# m328p.net
KiCad netlist of a schematic drawn in EAGLE
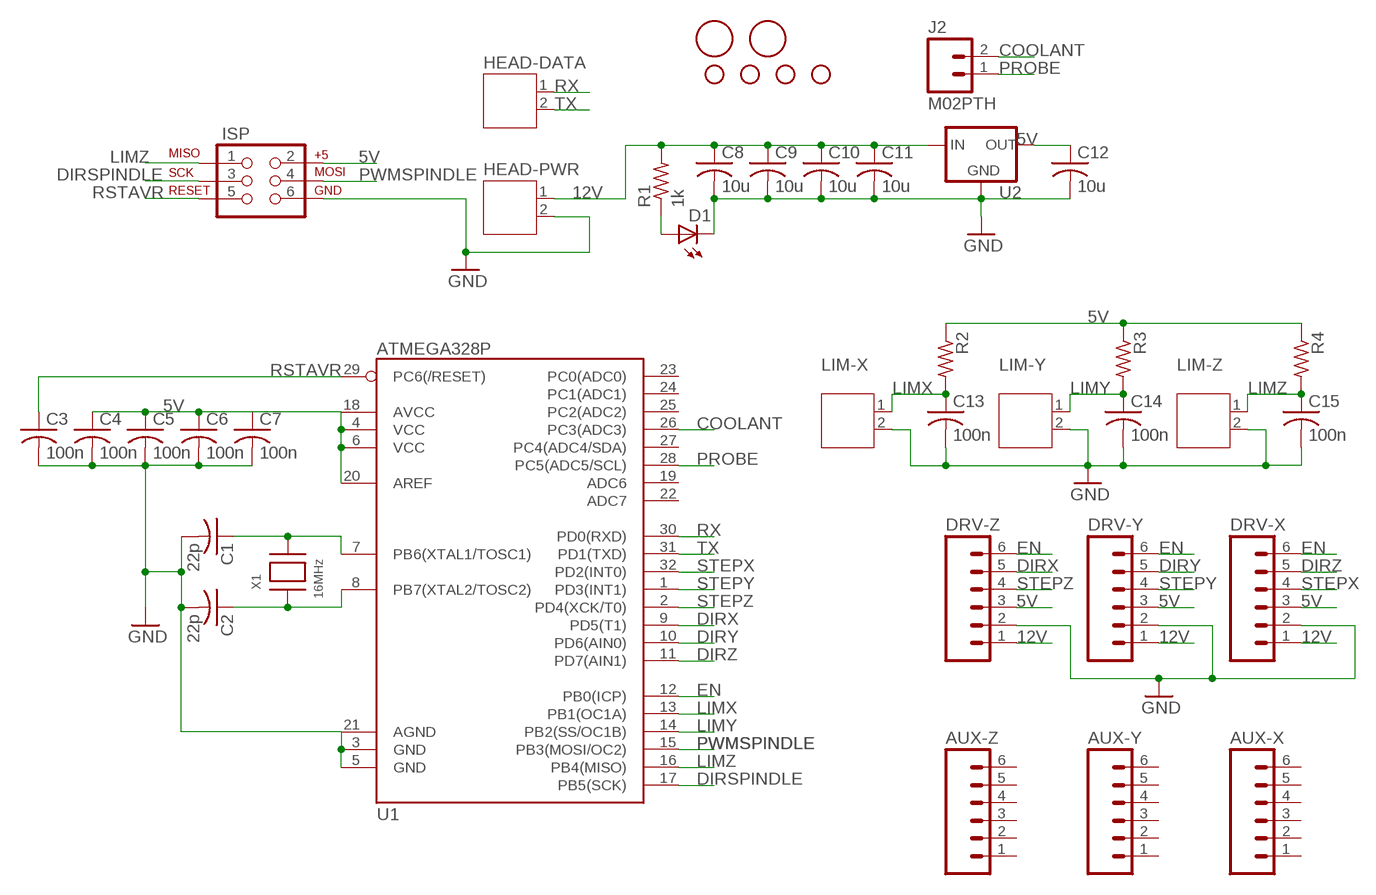
[diagram p0: schematic, sheet 1]

(export (version "E")
  (design (tool "Eeschema 10.0.6"))
  (components
    (comp (ref "AUX-X")
      (value "M06LOCK")
      (footprint "eagle-import:1X06_LOCK")
      (libsource (lib "eagle-import") (part "M06LOCK"))
    )
    (comp (ref "AUX-Y")
      (value "M06LOCK")
      (footprint "eagle-import:1X06_LOCK")
      (libsource (lib "eagle-import") (part "M06LOCK"))
    )
    (comp (ref "AUX-Z")
      (value "M06LOCK")
      (footprint "eagle-import:1X06_LOCK")
      (libsource (lib "eagle-import") (part "M06LOCK"))
    )
    (comp (ref "C1")
      (value "22p")
      (footprint "eagle-import:C0603")
      (libsource (lib "eagle-import") (part "C-USC0603"))
    )
    (comp (ref "C2")
      (value "22p")
      (footprint "eagle-import:C0603")
      (libsource (lib "eagle-import") (part "C-USC0603"))
    )
    (comp (ref "C3")
      (value "100n")
      (footprint "eagle-import:C0603")
      (libsource (lib "eagle-import") (part "C-USC0603"))
    )
    (comp (ref "C4")
      (value "100n")
      (footprint "eagle-import:C0603")
      (libsource (lib "eagle-import") (part "C-USC0603"))
    )
    (comp (ref "C5")
      (value "100n")
      (footprint "eagle-import:C0603")
      (libsource (lib "eagle-import") (part "C-USC0603"))
    )
    (comp (ref "C6")
      (value "100n")
      (footprint "eagle-import:C0603")
      (libsource (lib "eagle-import") (part "C-USC0603"))
    )
    (comp (ref "C7")
      (value "100n")
      (footprint "eagle-import:C0603")
      (libsource (lib "eagle-import") (part "C-USC0603"))
    )
    (comp (ref "C8")
      (value "10u")
      (footprint "eagle-import:C1206")
      (libsource (lib "eagle-import") (part "C-USC1206"))
    )
    (comp (ref "C9")
      (value "10u")
      (footprint "eagle-import:C1206")
      (libsource (lib "eagle-import") (part "C-USC1206"))
    )
    (comp (ref "C10")
      (value "10u")
      (footprint "eagle-import:C1206")
      (libsource (lib "eagle-import") (part "C-USC1206"))
    )
    (comp (ref "C11")
      (value "10u")
      (footprint "eagle-import:C1206")
      (libsource (lib "eagle-import") (part "C-USC1206"))
    )
    (comp (ref "C12")
      (value "10u")
      (footprint "eagle-import:C1206")
      (libsource (lib "eagle-import") (part "C-USC1206"))
    )
    (comp (ref "C13")
      (value "100n")
      (footprint "eagle-import:C0603")
      (libsource (lib "eagle-import") (part "C-USC0603"))
    )
    (comp (ref "C14")
      (value "100n")
      (footprint "eagle-import:C0603")
      (libsource (lib "eagle-import") (part "C-USC0603"))
    )
    (comp (ref "C15")
      (value "100n")
      (footprint "eagle-import:C0603")
      (libsource (lib "eagle-import") (part "C-USC0603"))
    )
    (comp (ref "D1")
      (value "LEDCHIPLED_1206")
      (footprint "eagle-import:CHIPLED_1206")
      (libsource (lib "eagle-import") (part "LEDCHIPLED_1206"))
    )
    (comp (ref "DRV-X")
      (value "M06LOCK")
      (footprint "eagle-import:1X06_LOCK")
      (libsource (lib "eagle-import") (part "M06LOCK"))
    )
    (comp (ref "DRV-Y")
      (value "M06LOCK")
      (footprint "eagle-import:1X06_LOCK")
      (libsource (lib "eagle-import") (part "M06LOCK"))
    )
    (comp (ref "DRV-Z")
      (value "M06LOCK")
      (footprint "eagle-import:1X06_LOCK")
      (libsource (lib "eagle-import") (part "M06LOCK"))
    )
    (comp (ref "HEAD-DATA")
      (value "JST-PH2")
      (footprint "eagle-import:JST-PH2")
      (libsource (lib "eagle-import") (part "JST-PH2"))
    )
    (comp (ref "HEAD-PWR")
      (value "JST-PH2")
      (footprint "eagle-import:JST-PH2")
      (libsource (lib "eagle-import") (part "JST-PH2"))
    )
    (comp (ref "ISP")
      (value "AVR_SPI_PRG_6PTH")
      (footprint "eagle-import:2X3")
      (libsource (lib "eagle-import") (part "AVR_SPI_PRG_6PTH"))
    )
    (comp (ref "J2")
      (value "M02PTH")
      (footprint "eagle-import:1X02")
      (libsource (lib "eagle-import") (part "M02PTH"))
    )
    (comp (ref "LIM-X")
      (value "JST-PH2")
      (footprint "eagle-import:JST-PH2")
      (libsource (lib "eagle-import") (part "JST-PH2"))
    )
    (comp (ref "LIM-Y")
      (value "JST-PH2")
      (footprint "eagle-import:JST-PH2")
      (libsource (lib "eagle-import") (part "JST-PH2"))
    )
    (comp (ref "LIM-Z")
      (value "JST-PH2")
      (footprint "eagle-import:JST-PH2")
      (libsource (lib "eagle-import") (part "JST-PH2"))
    )
    (comp (ref "R1")
      (value "1k")
      (footprint "eagle-import:R1206")
      (libsource (lib "eagle-import") (part "R-US_R1206"))
    )
    (comp (ref "R2")
      (value "R-US_R0603")
      (footprint "eagle-import:R0603")
      (libsource (lib "eagle-import") (part "R-US_R0603"))
    )
    (comp (ref "R3")
      (value "R-US_R0603")
      (footprint "eagle-import:R0603")
      (libsource (lib "eagle-import") (part "R-US_R0603"))
    )
    (comp (ref "R4")
      (value "R-US_R0603")
      (footprint "eagle-import:R0603")
      (libsource (lib "eagle-import") (part "R-US_R0603"))
    )
    (comp (ref "STANDOFF1")
      (value "STAND-OFFTIGHT")
      (footprint "eagle-import:STAND-OFF-TIGHT")
      (libsource (lib "eagle-import") (part "STAND-OFFTIGHT"))
    )
    (comp (ref "STANDOFF2")
      (value "STAND-OFFTIGHT")
      (footprint "eagle-import:STAND-OFF-TIGHT")
      (libsource (lib "eagle-import") (part "STAND-OFFTIGHT"))
    )
    (comp (ref "STANDOFF3")
      (value "STAND-OFFTIGHT")
      (footprint "eagle-import:STAND-OFF-TIGHT")
      (libsource (lib "eagle-import") (part "STAND-OFFTIGHT"))
    )
    (comp (ref "STANDOFF4")
      (value "STAND-OFFTIGHT")
      (footprint "eagle-import:STAND-OFF-TIGHT")
      (libsource (lib "eagle-import") (part "STAND-OFFTIGHT"))
    )
    (comp (ref "U$1")
      (value "FIDUCIAL")
      (footprint "eagle-import:FIDUCIAL_1MM")
      (libsource (lib "eagle-import") (part "FIDUCIAL"))
    )
    (comp (ref "U$2")
      (value "FIDUCIAL")
      (footprint "eagle-import:FIDUCIAL_1MM")
      (libsource (lib "eagle-import") (part "FIDUCIAL"))
    )
    (comp (ref "U1")
      (value "ATMEGA328P")
      (footprint "eagle-import:TQFP32-08")
      (libsource (lib "eagle-import") (part "ATMEGA328_SMT"))
    )
    (comp (ref "U2")
      (value "V_REG_MIC2920")
      (footprint "eagle-import:SOT223")
      (libsource (lib "eagle-import") (part "V_REG_MIC2920"))
    )
    (comp (ref "X1")
      (value "16MHz")
      (footprint "eagle-import:XTAL3215")
      (libsource (lib "eagle-import") (part "XTAL-3.2X1.5"))
    )
  )
  (nets
    (net (code "1") (name "/5V") (class "Default")
      (node (ref "C12") (pin "1") (pinfunction "1_1") (pintype "passive"))
      (node (ref "C4") (pin "1") (pinfunction "1_1") (pintype "passive"))
      (node (ref "C5") (pin "1") (pinfunction "1_1") (pintype "passive"))
      (node (ref "C6") (pin "1") (pinfunction "1_1") (pintype "passive"))
      (node (ref "C7") (pin "1") (pinfunction "1_1") (pintype "passive"))
      (node (ref "DRV-X") (pin "3") (pinfunction "3_3") (pintype "passive"))
      (node (ref "DRV-Y") (pin "3") (pinfunction "3_3") (pintype "passive"))
      (node (ref "DRV-Z") (pin "3") (pinfunction "3_3") (pintype "passive"))
      (node (ref "ISP") (pin "2") (pinfunction "2_2") (pintype "passive"))
      (node (ref "R2") (pin "1") (pinfunction "1_1") (pintype "passive"))
      (node (ref "R3") (pin "1") (pinfunction "1_1") (pintype "passive"))
      (node (ref "R4") (pin "1") (pinfunction "1_1") (pintype "passive"))
      (node (ref "U1") (pin "18") (pinfunction "AVCC_18") (pintype "bidirectional"))
      (node (ref "U1") (pin "20") (pinfunction "AREF_20") (pintype "bidirectional"))
      (node (ref "U1") (pin "4") (pinfunction "VCC_4") (pintype "bidirectional"))
      (node (ref "U1") (pin "6") (pinfunction "VCC_6") (pintype "bidirectional"))
      (node (ref "U2") (pin "3") (pinfunction "OUT_3") (pintype "output"))
    )
    (net (code "2") (name "/12V") (class "Default")
      (node (ref "C10") (pin "1") (pinfunction "1_1") (pintype "passive"))
      (node (ref "C11") (pin "1") (pinfunction "1_1") (pintype "passive"))
      (node (ref "C8") (pin "1") (pinfunction "1_1") (pintype "passive"))
      (node (ref "C9") (pin "1") (pinfunction "1_1") (pintype "passive"))
      (node (ref "DRV-X") (pin "1") (pinfunction "1_1") (pintype "passive"))
      (node (ref "DRV-Y") (pin "1") (pinfunction "1_1") (pintype "passive"))
      (node (ref "DRV-Z") (pin "1") (pinfunction "1_1") (pintype "passive"))
      (node (ref "HEAD-PWR") (pin "1") (pinfunction "1_1") (pintype "passive"))
      (node (ref "R1") (pin "2") (pinfunction "2_2") (pintype "passive"))
      (node (ref "U2") (pin "1") (pinfunction "IN_1") (pintype "input"))
    )
    (net (code "3") (name "/COOLANT") (class "Default")
      (node (ref "J2") (pin "2") (pinfunction "2_2") (pintype "passive"))
      (node (ref "U1") (pin "26") (pinfunction "PC3(ADC3)_26") (pintype "bidirectional"))
    )
    (net (code "4") (name "/DIRSPINDLE") (class "Default")
      (node (ref "ISP") (pin "3") (pinfunction "3_3") (pintype "passive"))
      (node (ref "U1") (pin "17") (pinfunction "PB5(SCK)_17") (pintype "bidirectional"))
    )
    (net (code "5") (name "/DIRX") (class "Default")
      (node (ref "DRV-Z") (pin "5") (pinfunction "5_5") (pintype "passive"))
      (node (ref "U1") (pin "9") (pinfunction "PD5(T1)_9") (pintype "bidirectional"))
    )
    (net (code "6") (name "/DIRY") (class "Default")
      (node (ref "DRV-Y") (pin "5") (pinfunction "5_5") (pintype "passive"))
      (node (ref "U1") (pin "10") (pinfunction "PD6(AIN0)_10") (pintype "bidirectional"))
    )
    (net (code "7") (name "/DIRZ") (class "Default")
      (node (ref "DRV-X") (pin "5") (pinfunction "5_5") (pintype "passive"))
      (node (ref "U1") (pin "11") (pinfunction "PD7(AIN1)_11") (pintype "bidirectional"))
    )
    (net (code "8") (name "/EN") (class "Default")
      (node (ref "DRV-X") (pin "6") (pinfunction "6_6") (pintype "passive"))
      (node (ref "DRV-Y") (pin "6") (pinfunction "6_6") (pintype "passive"))
      (node (ref "DRV-Z") (pin "6") (pinfunction "6_6") (pintype "passive"))
      (node (ref "U1") (pin "12") (pinfunction "PB0(ICP)_12") (pintype "bidirectional"))
    )
    (net (code "9") (name "/LIMX") (class "Default")
      (node (ref "C13") (pin "1") (pinfunction "1_1") (pintype "passive"))
      (node (ref "LIM-X") (pin "1") (pinfunction "1_1") (pintype "passive"))
      (node (ref "R2") (pin "2") (pinfunction "2_2") (pintype "passive"))
      (node (ref "U1") (pin "13") (pinfunction "PB1(OC1A)_13") (pintype "bidirectional"))
    )
    (net (code "10") (name "/LIMY") (class "Default")
      (node (ref "C14") (pin "1") (pinfunction "1_1") (pintype "passive"))
      (node (ref "LIM-Y") (pin "1") (pinfunction "1_1") (pintype "passive"))
      (node (ref "R3") (pin "2") (pinfunction "2_2") (pintype "passive"))
      (node (ref "U1") (pin "14") (pinfunction "PB2(SS/OC1B)_14") (pintype "bidirectional"))
    )
    (net (code "11") (name "/LIMZ") (class "Default")
      (node (ref "C15") (pin "1") (pinfunction "1_1") (pintype "passive"))
      (node (ref "ISP") (pin "1") (pinfunction "1_1") (pintype "passive"))
      (node (ref "LIM-Z") (pin "1") (pinfunction "1_1") (pintype "passive"))
      (node (ref "R4") (pin "2") (pinfunction "2_2") (pintype "passive"))
      (node (ref "U1") (pin "16") (pinfunction "PB4(MISO)_16") (pintype "bidirectional"))
    )
    (net (code "12") (name "/PROBE") (class "Default")
      (node (ref "J2") (pin "1") (pinfunction "1_1") (pintype "passive"))
      (node (ref "U1") (pin "28") (pinfunction "PC5(ADC5/SCL)_28") (pintype "bidirectional"))
    )
    (net (code "13") (name "/PWMSPINDLE") (class "Default")
      (node (ref "ISP") (pin "4") (pinfunction "4_4") (pintype "passive"))
      (node (ref "U1") (pin "15") (pinfunction "PB3(MOSI/OC2)_15") (pintype "bidirectional"))
    )
    (net (code "14") (name "/RSTAVR") (class "Default")
      (node (ref "C3") (pin "1") (pinfunction "1_1") (pintype "passive"))
      (node (ref "ISP") (pin "5") (pinfunction "5_5") (pintype "passive"))
      (node (ref "U1") (pin "29") (pinfunction "PC6(/RESET)_29") (pintype "bidirectional"))
    )
    (net (code "15") (name "/RX") (class "Default")
      (node (ref "HEAD-DATA") (pin "1") (pinfunction "1_1") (pintype "passive"))
      (node (ref "U1") (pin "30") (pinfunction "PD0(RXD)_30") (pintype "bidirectional"))
    )
    (net (code "16") (name "/STEPX") (class "Default")
      (node (ref "DRV-X") (pin "4") (pinfunction "4_4") (pintype "passive"))
      (node (ref "U1") (pin "32") (pinfunction "PD2(INT0)_32") (pintype "bidirectional"))
    )
    (net (code "17") (name "/STEPY") (class "Default")
      (node (ref "DRV-Y") (pin "4") (pinfunction "4_4") (pintype "passive"))
      (node (ref "U1") (pin "1") (pinfunction "PD3(INT1)_1") (pintype "bidirectional"))
    )
    (net (code "18") (name "/STEPZ") (class "Default")
      (node (ref "DRV-Z") (pin "4") (pinfunction "4_4") (pintype "passive"))
      (node (ref "U1") (pin "2") (pinfunction "PD4(XCK/T0)_2") (pintype "bidirectional"))
    )
    (net (code "19") (name "/TX") (class "Default")
      (node (ref "HEAD-DATA") (pin "2") (pinfunction "2_2") (pintype "passive"))
      (node (ref "U1") (pin "31") (pinfunction "PD1(TXD)_31") (pintype "bidirectional"))
    )
    (net (code "20") (name "GND") (class "Default")
      (node (ref "C1") (pin "2") (pinfunction "2_2") (pintype "passive"))
      (node (ref "C10") (pin "2") (pinfunction "2_2") (pintype "passive"))
      (node (ref "C11") (pin "2") (pinfunction "2_2") (pintype "passive"))
      (node (ref "C12") (pin "2") (pinfunction "2_2") (pintype "passive"))
      (node (ref "C13") (pin "2") (pinfunction "2_2") (pintype "passive"))
      (node (ref "C14") (pin "2") (pinfunction "2_2") (pintype "passive"))
      (node (ref "C15") (pin "2") (pinfunction "2_2") (pintype "passive"))
      (node (ref "C2") (pin "2") (pinfunction "2_2") (pintype "passive"))
      (node (ref "C3") (pin "2") (pinfunction "2_2") (pintype "passive"))
      (node (ref "C4") (pin "2") (pinfunction "2_2") (pintype "passive"))
      (node (ref "C5") (pin "2") (pinfunction "2_2") (pintype "passive"))
      (node (ref "C6") (pin "2") (pinfunction "2_2") (pintype "passive"))
      (node (ref "C7") (pin "2") (pinfunction "2_2") (pintype "passive"))
      (node (ref "C8") (pin "2") (pinfunction "2_2") (pintype "passive"))
      (node (ref "C9") (pin "2") (pinfunction "2_2") (pintype "passive"))
      (node (ref "D1") (pin "C") (pinfunction "C_C") (pintype "passive"))
      (node (ref "DRV-X") (pin "2") (pinfunction "2_2") (pintype "passive"))
      (node (ref "DRV-Y") (pin "2") (pinfunction "2_2") (pintype "passive"))
      (node (ref "DRV-Z") (pin "2") (pinfunction "2_2") (pintype "passive"))
      (node (ref "HEAD-PWR") (pin "2") (pinfunction "2_2") (pintype "passive"))
      (node (ref "ISP") (pin "6") (pinfunction "6_6") (pintype "passive"))
      (node (ref "LIM-X") (pin "2") (pinfunction "2_2") (pintype "passive"))
      (node (ref "LIM-Y") (pin "2") (pinfunction "2_2") (pintype "passive"))
      (node (ref "LIM-Z") (pin "2") (pinfunction "2_2") (pintype "passive"))
      (node (ref "U1") (pin "21") (pinfunction "AGND_21") (pintype "bidirectional"))
      (node (ref "U1") (pin "3") (pinfunction "GND_3") (pintype "bidirectional"))
      (node (ref "U1") (pin "5") (pinfunction "GND_5") (pintype "bidirectional"))
      (node (ref "U2") (pin "2") (pinfunction "GND_2") (pintype "input"))
      (node (ref "U2") (pin "4") (pinfunction "GND_4") (pintype "input"))
    )
    (net (code "21") (name "Net-(D1-PadA)") (class "Default")
      (node (ref "D1") (pin "A") (pinfunction "A_A") (pintype "passive"))
      (node (ref "R1") (pin "1") (pinfunction "1_1") (pintype "passive"))
    )
    (net (code "22") (name "Net-(U1-PB6(XTAL1{slash}TOSC1))") (class "Default")
      (node (ref "C1") (pin "1") (pinfunction "1_1") (pintype "passive"))
      (node (ref "U1") (pin "7") (pinfunction "PB6(XTAL1/TOSC1)_7") (pintype "bidirectional"))
      (node (ref "X1") (pin "P$2") (pinfunction "P$2_P$2") (pintype "bidirectional"))
    )
    (net (code "23") (name "Net-(U1-PB7(XTAL2{slash}TOSC2))") (class "Default")
      (node (ref "C2") (pin "1") (pinfunction "1_1") (pintype "passive"))
      (node (ref "U1") (pin "8") (pinfunction "PB7(XTAL2/TOSC2)_8") (pintype "bidirectional"))
      (node (ref "X1") (pin "P$1") (pinfunction "P$1_P$1") (pintype "bidirectional"))
    )
    (net (code "24") (name "unconnected-(AUX-X-Pad1)") (class "Default")
      (node (ref "AUX-X") (pin "1") (pinfunction "1_1") (pintype "passive"))
    )
    (net (code "25") (name "unconnected-(AUX-X-Pad2)") (class "Default")
      (node (ref "AUX-X") (pin "2") (pinfunction "2_2") (pintype "passive"))
    )
    (net (code "26") (name "unconnected-(AUX-X-Pad3)") (class "Default")
      (node (ref "AUX-X") (pin "3") (pinfunction "3_3") (pintype "passive"))
    )
    (net (code "27") (name "unconnected-(AUX-X-Pad4)") (class "Default")
      (node (ref "AUX-X") (pin "4") (pinfunction "4_4") (pintype "passive"))
    )
    (net (code "28") (name "unconnected-(AUX-X-Pad5)") (class "Default")
      (node (ref "AUX-X") (pin "5") (pinfunction "5_5") (pintype "passive"))
    )
    (net (code "29") (name "unconnected-(AUX-X-Pad6)") (class "Default")
      (node (ref "AUX-X") (pin "6") (pinfunction "6_6") (pintype "passive"))
    )
    (net (code "30") (name "unconnected-(AUX-Y-Pad1)") (class "Default")
      (node (ref "AUX-Y") (pin "1") (pinfunction "1_1") (pintype "passive"))
    )
    (net (code "31") (name "unconnected-(AUX-Y-Pad2)") (class "Default")
      (node (ref "AUX-Y") (pin "2") (pinfunction "2_2") (pintype "passive"))
    )
    (net (code "32") (name "unconnected-(AUX-Y-Pad3)") (class "Default")
      (node (ref "AUX-Y") (pin "3") (pinfunction "3_3") (pintype "passive"))
    )
    (net (code "33") (name "unconnected-(AUX-Y-Pad4)") (class "Default")
      (node (ref "AUX-Y") (pin "4") (pinfunction "4_4") (pintype "passive"))
    )
    (net (code "34") (name "unconnected-(AUX-Y-Pad5)") (class "Default")
      (node (ref "AUX-Y") (pin "5") (pinfunction "5_5") (pintype "passive"))
    )
    (net (code "35") (name "unconnected-(AUX-Y-Pad6)") (class "Default")
      (node (ref "AUX-Y") (pin "6") (pinfunction "6_6") (pintype "passive"))
    )
    (net (code "36") (name "unconnected-(AUX-Z-Pad1)") (class "Default")
      (node (ref "AUX-Z") (pin "1") (pinfunction "1_1") (pintype "passive"))
    )
    (net (code "37") (name "unconnected-(AUX-Z-Pad2)") (class "Default")
      (node (ref "AUX-Z") (pin "2") (pinfunction "2_2") (pintype "passive"))
    )
    (net (code "38") (name "unconnected-(AUX-Z-Pad3)") (class "Default")
      (node (ref "AUX-Z") (pin "3") (pinfunction "3_3") (pintype "passive"))
    )
    (net (code "39") (name "unconnected-(AUX-Z-Pad4)") (class "Default")
      (node (ref "AUX-Z") (pin "4") (pinfunction "4_4") (pintype "passive"))
    )
    (net (code "40") (name "unconnected-(AUX-Z-Pad5)") (class "Default")
      (node (ref "AUX-Z") (pin "5") (pinfunction "5_5") (pintype "passive"))
    )
    (net (code "41") (name "unconnected-(AUX-Z-Pad6)") (class "Default")
      (node (ref "AUX-Z") (pin "6") (pinfunction "6_6") (pintype "passive"))
    )
    (net (code "42") (name "unconnected-(U1-ADC6-Pad19)") (class "Default")
      (node (ref "U1") (pin "19") (pinfunction "ADC6_19") (pintype "bidirectional"))
    )
    (net (code "43") (name "unconnected-(U1-ADC7-Pad22)") (class "Default")
      (node (ref "U1") (pin "22") (pinfunction "ADC7_22") (pintype "bidirectional"))
    )
    (net (code "44") (name "unconnected-(U1-PC0(ADC0)-Pad23)") (class "Default")
      (node (ref "U1") (pin "23") (pinfunction "PC0(ADC0)_23") (pintype "bidirectional"))
    )
    (net (code "45") (name "unconnected-(U1-PC1(ADC1)-Pad24)") (class "Default")
      (node (ref "U1") (pin "24") (pinfunction "PC1(ADC1)_24") (pintype "bidirectional"))
    )
    (net (code "46") (name "unconnected-(U1-PC2(ADC2)-Pad25)") (class "Default")
      (node (ref "U1") (pin "25") (pinfunction "PC2(ADC2)_25") (pintype "bidirectional"))
    )
    (net (code "47") (name "unconnected-(U1-PC4(ADC4{slash}SDA)-Pad27)") (class "Default")
      (node (ref "U1") (pin "27") (pinfunction "PC4(ADC4/SDA)_27") (pintype "bidirectional"))
    )
  )
)
